# WeatherStation_V2.net
KiCad netlist of a schematic drawn in Altium Designer
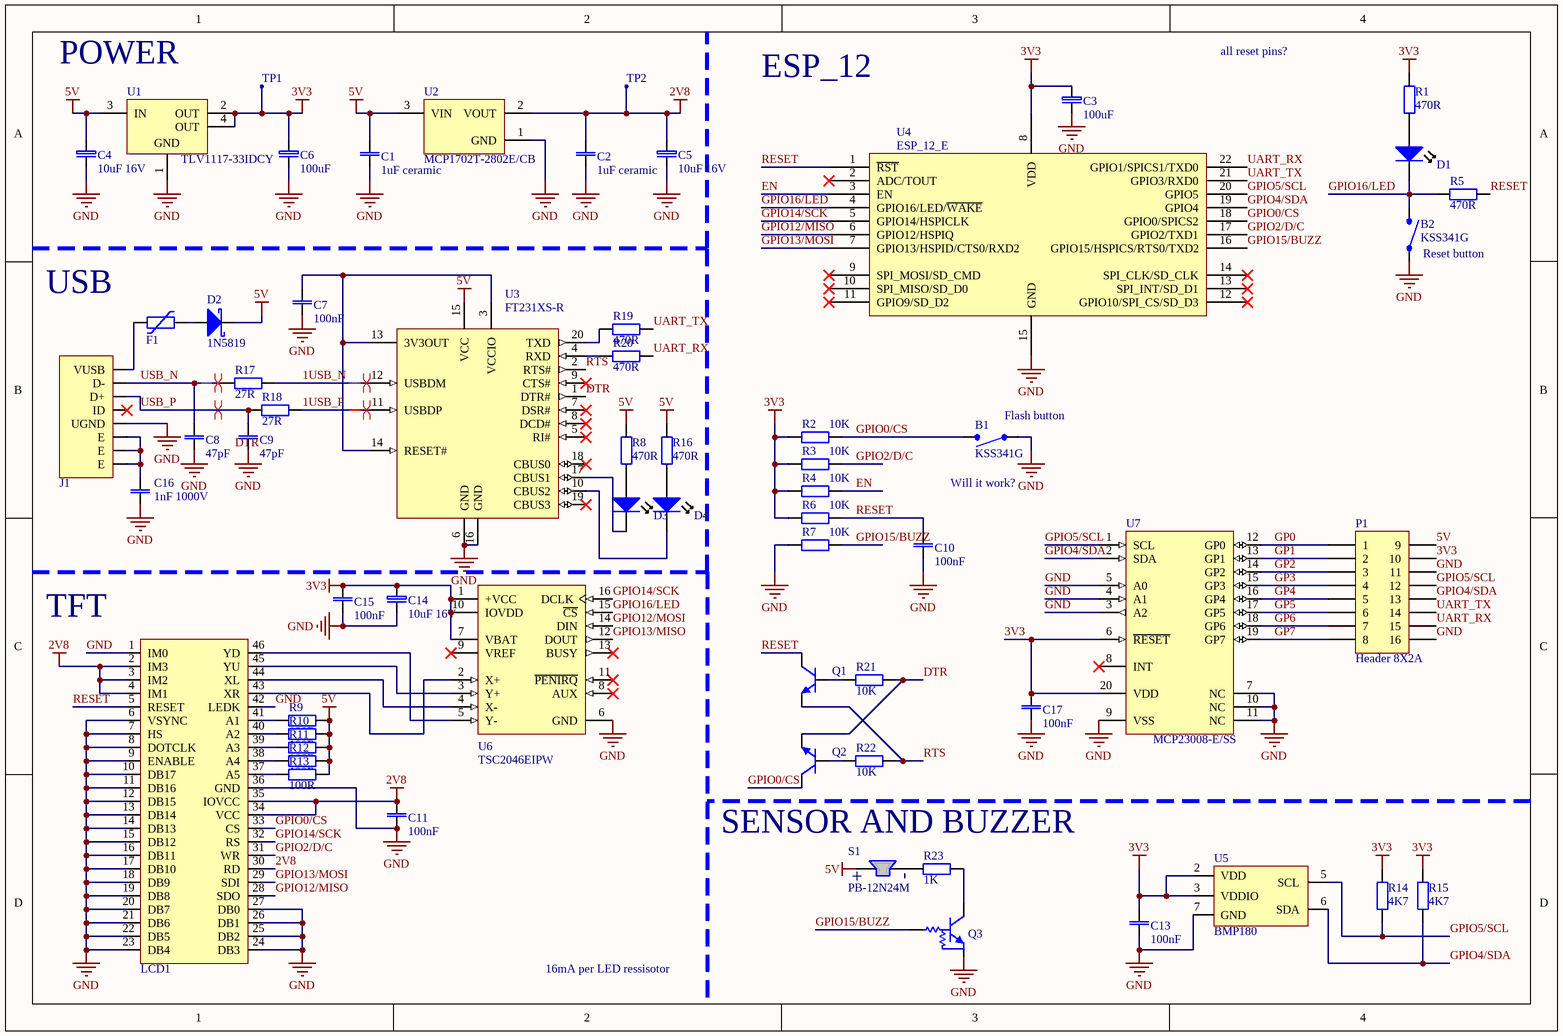
[diagram p0: WeatherStation_V2.SchDoc]

(export (version "E")
  (design (tool "Eeschema 10.0.6"))
  (components
    (comp (ref "B1")
      (value "KSS341G")
      (footprint "KSS341G")
      (description "side-mounted tactile button")
      (libsource (lib "DiscreteSchlib") (part "KSS341G"))
    )
    (comp (ref "B2")
      (value "KSS341G")
      (footprint "KSS341G")
      (description "side-mounted tactile button")
      (libsource (lib "DiscreteSchlib") (part "KSS341G"))
    )
    (comp (ref "C1")
      (value "1uF ceramic")
      (footprint "DiscretePcbLib:C0603")
      (description "SMD Capacitor")
      (libsource (lib "DiscreteSchlib") (part "C0603"))
    )
    (comp (ref "C2")
      (value "1uF ceramic")
      (footprint "DiscretePcbLib:C0603")
      (description "SMD Capacitor")
      (libsource (lib "DiscreteSchlib") (part "C0603"))
    )
    (comp (ref "C3")
      (value "100uF")
      (footprint "DiscretePcbLib:CASE B")
      (description "Tantalum capacitor")
      (libsource (lib "DiscreteSchlib") (part "Case B"))
    )
    (comp (ref "C4")
      (value "10uF 16V")
      (footprint "DiscretePcbLib:Case A")
      (description "Tantalum capacitor")
      (libsource (lib "DiscreteSchlib") (part "Case A"))
    )
    (comp (ref "C5")
      (value "10uF 16V")
      (footprint "DiscretePcbLib:Case A")
      (description "Tantalum capacitor")
      (libsource (lib "DiscreteSchlib") (part "Case A"))
    )
    (comp (ref "C6")
      (value "100uF")
      (footprint "DiscretePcbLib:CASE B")
      (description "Tantalum capacitor")
      (libsource (lib "DiscreteSchlib") (part "Case B"))
    )
    (comp (ref "C7")
      (value "100nF")
      (footprint "DiscretePcbLib:C0603")
      (description "SMD Capacitor")
      (libsource (lib "DiscreteSchlib") (part "C0603"))
    )
    (comp (ref "C8")
      (value "47pF")
      (footprint "DiscretePcbLib:C0603")
      (description "SMD Capacitor")
      (libsource (lib "DiscreteSchlib") (part "C0603"))
    )
    (comp (ref "C9")
      (value "47pF")
      (footprint "DiscretePcbLib:C0603")
      (description "SMD Capacitor")
      (libsource (lib "DiscreteSchlib") (part "C0603"))
    )
    (comp (ref "C10")
      (value "100nF")
      (footprint "DiscretePcbLib:C0603")
      (description "SMD Capacitor")
      (libsource (lib "DiscreteSchlib") (part "C0603"))
    )
    (comp (ref "C11")
      (value "100nF")
      (footprint "DiscretePcbLib:C0603")
      (description "SMD Capacitor")
      (libsource (lib "DiscreteSchlib") (part "C0603"))
    )
    (comp (ref "C13")
      (value "100nF")
      (footprint "DiscretePcbLib:C0603")
      (description "SMD Capacitor")
      (libsource (lib "DiscreteSchlib") (part "C0603"))
    )
    (comp (ref "C14")
      (value "10uF 16V")
      (footprint "DiscretePcbLib:Case A")
      (description "Tantalum capacitor")
      (libsource (lib "DiscreteSchlib") (part "Case A"))
    )
    (comp (ref "C15")
      (value "100nF")
      (footprint "DiscretePcbLib:C0603")
      (description "SMD Capacitor")
      (libsource (lib "DiscreteSchlib") (part "C0603"))
    )
    (comp (ref "C16")
      (value "1nF 1000V")
      (footprint "DiscretePcbLib:C1206")
      (description "SMD Capacitor")
      (libsource (lib "DiscreteSchlib") (part "C1206"))
    )
    (comp (ref "C17")
      (value "100nF")
      (footprint "DiscretePcbLib:C0603")
      (description "SMD Capacitor")
      (libsource (lib "DiscreteSchlib") (part "C0603"))
    )
    (comp (ref "D1")
      (value "BLUE LED")
      (footprint "DiscretePcbLib:LED0805B")
      (description "BLUE SMD LED 0805")
      (libsource (lib "DiscreteSchlib") (part "LED0805B"))
    )
    (comp (ref "D2")
      (value "1N5819")
      (footprint "1N5819-SMA")
      (description "40V 1A UFM0.5V/1A IFM30A IR0.4mA, Schottky")
      (libsource (lib "DiscreteSchlib") (part "1N5819(SS14)"))
    )
    (comp (ref "D3")
      (value "GREEN LED")
      (footprint "DiscretePcbLib:LED0805G")
      (description "GREEN SMD LED 0805")
      (libsource (lib "DiscreteSchlib") (part "LED0805G"))
    )
    (comp (ref "D4")
      (value "GREEN LED")
      (footprint "DiscretePcbLib:LED0805G")
      (description "GREEN SMD LED 0805")
      (libsource (lib "DiscreteSchlib") (part "LED0805G"))
    )
    (comp (ref "F1")
      (value "MF-MSMF075-2")
      (footprint "DiscretePcbLib:F1812")
      (description "Resettable Fuse 1812")
      (libsource (lib "DiscreteSchlib") (part "PFMF.XXX.X"))
    )
    (comp (ref "J1")
      (value "USB B MICRO R/A SMD 1")
      (footprint "DiscretePcbLib:USB B MICRO R/A SMD 1")
      (libsource (lib "DiscreteSchlib") (part "USB B MICRO R/A SMD 1"))
    )
    (comp (ref "LCD1")
      (value "KWH032ST05-F02")
      (footprint "KWH032ST05-F02")
      (libsource (lib "Schlib2") (part "KWH032ST05-F02"))
    )
    (comp (ref "P1")
      (value "Header 8X2A")
      (footprint "HDR2X8_CEN")
      (description "Header, 8-Pin, Dual row")
      (fields (field (name "PUBLISHER") "Altium Limited"))
      (libsource (lib "Miscellaneous Connectors") (part "Header 8X2A"))
    )
    (comp (ref "Q1")
      (value "BC817")
      (footprint "DiscretePcbLib:SOT23")
      (description "NPN SOT23")
      (libsource (lib "DiscreteSchlib") (part "BC817"))
    )
    (comp (ref "Q2")
      (value "BC817")
      (footprint "DiscretePcbLib:SOT23")
      (description "NPN SOT23")
      (libsource (lib "DiscreteSchlib") (part "BC817"))
    )
    (comp (ref "Q3")
      (value "PDTC123JT")
      (footprint "DiscretePcbLib:SOT23")
      (description "DIGI TRANS Rin 2.2k Rbe 47k NPN 50V 100mA")
      (libsource (lib "DiscreteSchlib") (part "PDTC123JT"))
    )
    (comp (ref "R1")
      (value "470R")
      (footprint "DiscretePcbLib:R0603")
      (description "SMD Resistor")
      (libsource (lib "") (part "R0603_2"))
    )
    (comp (ref "R2")
      (value "10K")
      (footprint "DiscretePcbLib:R0603")
      (description "SMD Resistor")
      (libsource (lib "DiscreteSchlib") (part "R0603"))
    )
    (comp (ref "R3")
      (value "10K")
      (footprint "DiscretePcbLib:R0603")
      (description "SMD Resistor")
      (libsource (lib "DiscreteSchlib") (part "R0603"))
    )
    (comp (ref "R4")
      (value "10K")
      (footprint "DiscretePcbLib:R0603")
      (description "SMD Resistor")
      (libsource (lib "DiscreteSchlib") (part "R0603"))
    )
    (comp (ref "R5")
      (value "470R")
      (footprint "DiscretePcbLib:R0603")
      (description "SMD Resistor")
      (libsource (lib "DiscreteSchlib") (part "R0603"))
    )
    (comp (ref "R6")
      (value "10K")
      (footprint "DiscretePcbLib:R0603")
      (description "SMD Resistor")
      (libsource (lib "DiscreteSchlib") (part "R0603"))
    )
    (comp (ref "R7")
      (value "10K")
      (footprint "DiscretePcbLib:R0603")
      (description "SMD Resistor")
      (libsource (lib "DiscreteSchlib") (part "R0603"))
    )
    (comp (ref "R8")
      (value "470R")
      (footprint "DiscretePcbLib:R0603")
      (description "SMD Resistor")
      (libsource (lib "") (part "R0603_1"))
    )
    (comp (ref "R9")
      (value "100R")
      (footprint "DiscretePcbLib:R0603")
      (description "SMD Resistor")
      (libsource (lib "DiscreteSchlib") (part "R0603"))
    )
    (comp (ref "R10")
      (value "100R")
      (footprint "DiscretePcbLib:R0603")
      (description "SMD Resistor")
      (libsource (lib "DiscreteSchlib") (part "R0603"))
    )
    (comp (ref "R11")
      (value "100R")
      (footprint "DiscretePcbLib:R0603")
      (description "SMD Resistor")
      (libsource (lib "DiscreteSchlib") (part "R0603"))
    )
    (comp (ref "R12")
      (value "100R")
      (footprint "DiscretePcbLib:R0603")
      (description "SMD Resistor")
      (libsource (lib "DiscreteSchlib") (part "R0603"))
    )
    (comp (ref "R13")
      (value "100R")
      (footprint "DiscretePcbLib:R0603")
      (description "SMD Resistor")
      (libsource (lib "DiscreteSchlib") (part "R0603"))
    )
    (comp (ref "R14")
      (value "4K7")
      (footprint "DiscretePcbLib:R0603")
      (description "SMD Resistor")
      (libsource (lib "") (part "R0603_1"))
    )
    (comp (ref "R15")
      (value "4K7")
      (footprint "DiscretePcbLib:R0603")
      (description "SMD Resistor")
      (libsource (lib "") (part "R0603_1"))
    )
    (comp (ref "R16")
      (value "470R")
      (footprint "DiscretePcbLib:R0603")
      (description "SMD Resistor")
      (libsource (lib "") (part "R0603_1"))
    )
    (comp (ref "R17")
      (value "27R")
      (footprint "DiscretePcbLib:R0603")
      (description "SMD Resistor")
      (libsource (lib "DiscreteSchlib") (part "R0603"))
    )
    (comp (ref "R18")
      (value "27R")
      (footprint "DiscretePcbLib:R0603")
      (description "SMD Resistor")
      (libsource (lib "DiscreteSchlib") (part "R0603"))
    )
    (comp (ref "R19")
      (value "470R")
      (footprint "DiscretePcbLib:R0603")
      (description "SMD Resistor")
      (libsource (lib "DiscreteSchlib") (part "R0603"))
    )
    (comp (ref "R20")
      (value "470R")
      (footprint "DiscretePcbLib:R0603")
      (description "SMD Resistor")
      (libsource (lib "DiscreteSchlib") (part "R0603"))
    )
    (comp (ref "R21")
      (value "10K")
      (footprint "DiscretePcbLib:R0603")
      (description "SMD Resistor")
      (libsource (lib "DiscreteSchlib") (part "R0603"))
    )
    (comp (ref "R22")
      (value "10K")
      (footprint "DiscretePcbLib:R0603")
      (description "SMD Resistor")
      (libsource (lib "DiscreteSchlib") (part "R0603"))
    )
    (comp (ref "R23")
      (value "1K")
      (footprint "DiscretePcbLib:R0603")
      (description "SMD Resistor")
      (libsource (lib "DiscreteSchlib") (part "R0603"))
    )
    (comp (ref "S1")
      (value "PB-12N24M")
      (footprint "PB-12N24M")
      (libsource (lib "DiscreteSchlib") (part "PB-12N24M"))
    )
    (comp (ref "TP1")
      (value "TestPoint_1.5mm")
      (footprint "DiscretePcbLib:TP_1.5mm")
      (description "TestPoint SMD pad 1.5mm")
      (libsource (lib "DiscreteSchlib") (part "TestPoint_1.5mm"))
    )
    (comp (ref "TP2")
      (value "TestPoint_1.5mm")
      (footprint "DiscretePcbLib:TP_1.5mm")
      (description "TestPoint SMD pad 1.5mm")
      (libsource (lib "DiscreteSchlib") (part "TestPoint_1.5mm"))
    )
    (comp (ref "U1")
      (value "TLV1117-33IDCY")
      (footprint "TI-DCY4_N")
      (fields (field (name "MANUFACTURER") "Texas Instruments") (field (name "PARTNUMBER") "TLV1117LV33DCYR"))
      (libsource (lib "TI Power Management Linear Regulator Single Channel LDO (400-7500mA)") (part "TLV1117LV33DCYR"))
    )
    (comp (ref "U2")
      (value "MCP1702T-2802E/CB")
      (footprint "SOT-23A-CB3_N")
      (description "250 mA Low Quiescent Current LDO Regulator, 3-Pin SOT-23A, Extended Temperature, Tape and Reel")
      (fields (field (name "MANUFACTURER") "Microchip"))
      (libsource (lib "Microchip Power Management Line Regulator") (part "MCP1702T-2802E/CB"))
    )
    (comp (ref "U3")
      (value "FT231XS-R")
      (footprint "SSOP-20_N")
      (fields (field (name "MANUFACTURER") "FTDI"))
      (libsource (lib "FTDI FT-X Series") (part "FT231XS-R"))
    )
    (comp (ref "U4")
      (value "ESP_12_E")
      (footprint "ESP-12Q/F")
      (description "ESP-12 Wi-Fi Module by AI-Thinker")
      (libsource (lib "DiscreteSchlib") (part "ESP_12_E"))
    )
    (comp (ref "U5")
      (value "BMP180")
      (footprint "BMP180")
      (description "temperature/pressure/altitude sensor")
      (libsource (lib "DiscreteSchlib") (part "BMP180"))
    )
    (comp (ref "U6")
      (value "TSC2046EIPW")
      (footprint "PW016")
      (description "4-Wire Touch Screen controller with Low-Voltage I/O Interface, 16-Pin TSSOP")
      (fields (field (name "PUBLISHER") "Altium Limited"))
      (libsource (lib "TI Interface Touch Screen Controller") (part "TSC2046EIPW"))
    )
    (comp (ref "U7")
      (value "MCP23008-E/SS")
      (footprint "SSOP-SS20_N")
      (description "8-Bit I/O Expander with Serial Interface, 20-Pin SSOP, Extended Temperature")
      (fields (field (name "MANUFACTURER") "Microchip"))
      (libsource (lib "Microchip Interface") (part "MCP23008-E/SS"))
    )
  )
  (nets
    (net (code "1") (name "/1USB_N") (class "Default")
      (node (ref "R17") (pin "2") (pinfunction "2_2") (pintype "passive"))
      (node (ref "U3") (pin "12") (pinfunction "USBDM_12") (pintype "input"))
    )
    (net (code "2") (name "/1USB_P") (class "Default")
      (node (ref "R18") (pin "2") (pinfunction "2_2") (pintype "passive"))
      (node (ref "U3") (pin "11") (pinfunction "USBDP_11") (pintype "input"))
    )
    (net (code "3") (name "/DTR") (class "Default")
      (node (ref "Q2") (pin "2") (pinfunction "2_2") (pintype "passive"))
      (node (ref "R21") (pin "2") (pinfunction "2_2") (pintype "passive"))
      (node (ref "U3") (pin "1") (pinfunction "DTR#_1") (pintype "output"))
    )
    (net (code "4") (name "/EN") (class "Default")
      (node (ref "R4") (pin "2") (pinfunction "2_2") (pintype "passive"))
      (node (ref "U4") (pin "3") (pinfunction "EN_3") (pintype "passive"))
    )
    (net (code "5") (name "/GP0") (class "Default")
      (node (ref "P1") (pin "1") (pinfunction "1_1") (pintype "passive"))
      (node (ref "U7") (pin "12") (pinfunction "GP0_12") (pintype "bidirectional"))
    )
    (net (code "6") (name "/GP1") (class "Default")
      (node (ref "P1") (pin "2") (pinfunction "2_2") (pintype "passive"))
      (node (ref "U7") (pin "13") (pinfunction "GP1_13") (pintype "bidirectional"))
    )
    (net (code "7") (name "/GP2") (class "Default")
      (node (ref "P1") (pin "3") (pinfunction "3_3") (pintype "passive"))
      (node (ref "U7") (pin "14") (pinfunction "GP2_14") (pintype "bidirectional"))
    )
    (net (code "8") (name "/GP3") (class "Default")
      (node (ref "P1") (pin "4") (pinfunction "4_4") (pintype "passive"))
      (node (ref "U7") (pin "15") (pinfunction "GP3_15") (pintype "bidirectional"))
    )
    (net (code "9") (name "/GP4") (class "Default")
      (node (ref "P1") (pin "5") (pinfunction "5_5") (pintype "passive"))
      (node (ref "U7") (pin "16") (pinfunction "GP4_16") (pintype "bidirectional"))
    )
    (net (code "10") (name "/GP5") (class "Default")
      (node (ref "P1") (pin "6") (pinfunction "6_6") (pintype "passive"))
      (node (ref "U7") (pin "17") (pinfunction "GP5_17") (pintype "bidirectional"))
    )
    (net (code "11") (name "/GP6") (class "Default")
      (node (ref "P1") (pin "7") (pinfunction "7_7") (pintype "passive"))
      (node (ref "U7") (pin "18") (pinfunction "GP6_18") (pintype "bidirectional"))
    )
    (net (code "12") (name "/GP7") (class "Default")
      (node (ref "P1") (pin "8") (pinfunction "8_8") (pintype "passive"))
      (node (ref "U7") (pin "19") (pinfunction "GP7_19") (pintype "bidirectional"))
    )
    (net (code "13") (name "/GPIO0{slash}CS") (class "Default")
      (node (ref "B1") (pin "2") (pinfunction "2_2") (pintype "passive"))
      (node (ref "LCD1") (pin "33") (pinfunction "CS_33") (pintype "passive"))
      (node (ref "Q2") (pin "3") (pinfunction "3_3") (pintype "passive"))
      (node (ref "R2") (pin "2") (pinfunction "2_2") (pintype "passive"))
      (node (ref "U4") (pin "18") (pinfunction "GPIO0/SPICS2_18") (pintype "passive"))
    )
    (net (code "14") (name "/GPIO2{slash}D{slash}C") (class "Default")
      (node (ref "LCD1") (pin "31") (pinfunction "WR_31") (pintype "passive"))
      (node (ref "R3") (pin "2") (pinfunction "2_2") (pintype "passive"))
      (node (ref "U4") (pin "17") (pinfunction "GPIO2/TXD1_17") (pintype "passive"))
    )
    (net (code "15") (name "/GPIO4{slash}SDA") (class "Default")
      (node (ref "P1") (pin "13") (pinfunction "13_13") (pintype "passive"))
      (node (ref "R15") (pin "1") (pinfunction "1_1") (pintype "passive"))
      (node (ref "U4") (pin "19") (pinfunction "GPIO4_19") (pintype "passive"))
      (node (ref "U5") (pin "6") (pinfunction "SDA_6") (pintype "passive"))
      (node (ref "U7") (pin "2") (pinfunction "SDA_2") (pintype "input"))
    )
    (net (code "16") (name "/GPIO5{slash}SCL") (class "Default")
      (node (ref "P1") (pin "12") (pinfunction "12_12") (pintype "passive"))
      (node (ref "R14") (pin "1") (pinfunction "1_1") (pintype "passive"))
      (node (ref "U4") (pin "20") (pinfunction "GPIO5_20") (pintype "passive"))
      (node (ref "U5") (pin "5") (pinfunction "SCL_5") (pintype "passive"))
      (node (ref "U7") (pin "1") (pinfunction "SCL_1") (pintype "input"))
    )
    (net (code "17") (name "/GPIO12{slash}MISO") (class "Default")
      (node (ref "LCD1") (pin "28") (pinfunction "SDO_28") (pintype "passive"))
      (node (ref "U4") (pin "6") (pinfunction "GPIO12/HSPIQ_6") (pintype "passive"))
    )
    (net (code "18") (name "/GPIO12{slash}MOSI") (class "Default")
      (node (ref "U6") (pin "14") (pinfunction "DIN_14") (pintype "input"))
    )
    (net (code "19") (name "/GPIO13{slash}MISO") (class "Default")
      (node (ref "U6") (pin "12") (pinfunction "DOUT_12") (pintype "output"))
    )
    (net (code "20") (name "/GPIO13{slash}MOSI") (class "Default")
      (node (ref "LCD1") (pin "29") (pinfunction "SDI_29") (pintype "passive"))
      (node (ref "U4") (pin "7") (pinfunction "GPIO13/HSPID/CTS0/RXD2_7") (pintype "passive"))
    )
    (net (code "21") (name "/GPIO14{slash}SCK") (class "Default")
      (node (ref "LCD1") (pin "32") (pinfunction "RS_32") (pintype "passive"))
      (node (ref "U4") (pin "5") (pinfunction "GPIO14/HSPICLK_5") (pintype "passive"))
      (node (ref "U6") (pin "16") (pinfunction "DCLK_16") (pintype "input"))
    )
    (net (code "22") (name "/GPIO15{slash}BUZZ") (class "Default")
      (node (ref "Q3") (pin "1") (pinfunction "1_1") (pintype "passive"))
      (node (ref "R7") (pin "2") (pinfunction "2_2") (pintype "passive"))
      (node (ref "U4") (pin "16") (pinfunction "GPIO15/HSPICS/RTS0/TXD2_16") (pintype "passive"))
    )
    (net (code "23") (name "/GPIO16{slash}LED") (class "Default")
      (node (ref "B2") (pin "2") (pinfunction "2_2") (pintype "passive"))
      (node (ref "D1") (pin "1") (pinfunction "1_1") (pintype "passive"))
      (node (ref "R5") (pin "1") (pinfunction "1_1") (pintype "passive"))
      (node (ref "U4") (pin "4") (pinfunction "GPIO16/LED/~{WAKE}_4") (pintype "passive"))
      (node (ref "U6") (pin "15") (pinfunction "~{CS}_15") (pintype "input"))
    )
    (net (code "24") (name "/RESET") (class "Default")
      (node (ref "C10") (pin "2") (pinfunction "2_2") (pintype "passive"))
      (node (ref "LCD1") (pin "5") (pinfunction "RESET_5") (pintype "passive"))
      (node (ref "Q1") (pin "3") (pinfunction "3_3") (pintype "passive"))
      (node (ref "R5") (pin "2") (pinfunction "2_2") (pintype "passive"))
      (node (ref "R6") (pin "2") (pinfunction "2_2") (pintype "passive"))
      (node (ref "U4") (pin "1") (pinfunction "~{RST}_1") (pintype "passive"))
    )
    (net (code "25") (name "/RTS") (class "Default")
      (node (ref "Q1") (pin "2") (pinfunction "2_2") (pintype "passive"))
      (node (ref "R22") (pin "2") (pinfunction "2_2") (pintype "passive"))
      (node (ref "U3") (pin "2") (pinfunction "RTS#_2") (pintype "output"))
    )
    (net (code "26") (name "/UART_RX") (class "Default")
      (node (ref "P1") (pin "15") (pinfunction "15_15") (pintype "passive"))
      (node (ref "R20") (pin "2") (pinfunction "2_2") (pintype "passive"))
      (node (ref "U4") (pin "22") (pinfunction "GPIO1/SPICS1/TXD0_22") (pintype "passive"))
    )
    (net (code "27") (name "/UART_TX") (class "Default")
      (node (ref "P1") (pin "14") (pinfunction "14_14") (pintype "passive"))
      (node (ref "R19") (pin "2") (pinfunction "2_2") (pintype "passive"))
      (node (ref "U4") (pin "21") (pinfunction "GPIO3/RXD0_21") (pintype "passive"))
    )
    (net (code "28") (name "/USB_N") (class "Default")
      (node (ref "C8") (pin "2") (pinfunction "2_2") (pintype "passive"))
      (node (ref "J1") (pin "2") (pinfunction "D-_2") (pintype "passive"))
      (node (ref "R17") (pin "1") (pinfunction "1_1") (pintype "passive"))
    )
    (net (code "29") (name "/USB_P") (class "Default")
      (node (ref "C9") (pin "2") (pinfunction "2_2") (pintype "passive"))
      (node (ref "J1") (pin "3") (pinfunction "D+_3") (pintype "passive"))
      (node (ref "R18") (pin "1") (pinfunction "1_1") (pintype "passive"))
    )
    (net (code "30") (name "2V8") (class "Default")
      (node (ref "C11") (pin "2") (pinfunction "2_2") (pintype "passive"))
      (node (ref "C2") (pin "2") (pinfunction "2_2") (pintype "passive"))
      (node (ref "C5") (pin "1") (pinfunction "1_1") (pintype "passive"))
      (node (ref "LCD1") (pin "2") (pinfunction "IM3_2") (pintype "passive"))
      (node (ref "LCD1") (pin "3") (pinfunction "IM2_3") (pintype "passive"))
      (node (ref "LCD1") (pin "30") (pinfunction "RD_30") (pintype "passive"))
      (node (ref "LCD1") (pin "34") (pinfunction "VCC_34") (pintype "passive"))
      (node (ref "LCD1") (pin "35") (pinfunction "IOVCC_35") (pintype "passive"))
      (node (ref "LCD1") (pin "4") (pinfunction "IM1_4") (pintype "passive"))
      (node (ref "TP2") (pin "1") (pinfunction "1_1") (pintype "passive"))
      (node (ref "U2") (pin "2") (pinfunction "VOUT_2") (pintype "power_in"))
    )
    (net (code "31") (name "3V3") (class "Default")
      (node (ref "C13") (pin "2") (pinfunction "2_2") (pintype "passive"))
      (node (ref "C14") (pin "1") (pinfunction "1_1") (pintype "passive"))
      (node (ref "C15") (pin "2") (pinfunction "2_2") (pintype "passive"))
      (node (ref "C17") (pin "2") (pinfunction "2_2") (pintype "passive"))
      (node (ref "C3") (pin "1") (pinfunction "1_1") (pintype "passive"))
      (node (ref "C6") (pin "1") (pinfunction "1_1") (pintype "passive"))
      (node (ref "P1") (pin "10") (pinfunction "10_10") (pintype "passive"))
      (node (ref "R1") (pin "1") (pinfunction "1_1") (pintype "passive"))
      (node (ref "R14") (pin "2") (pinfunction "2_2") (pintype "passive"))
      (node (ref "R15") (pin "2") (pinfunction "2_2") (pintype "passive"))
      (node (ref "R2") (pin "1") (pinfunction "1_1") (pintype "passive"))
      (node (ref "R3") (pin "1") (pinfunction "1_1") (pintype "passive"))
      (node (ref "R4") (pin "1") (pinfunction "1_1") (pintype "passive"))
      (node (ref "R6") (pin "1") (pinfunction "1_1") (pintype "passive"))
      (node (ref "TP1") (pin "1") (pinfunction "1_1") (pintype "passive"))
      (node (ref "U1") (pin "2") (pinfunction "OUT_2") (pintype "power_in"))
      (node (ref "U1") (pin "4") (pinfunction "OUT_4") (pintype "power_in"))
      (node (ref "U4") (pin "8") (pinfunction "VDD_8") (pintype "passive"))
      (node (ref "U5") (pin "2") (pinfunction "VDD_2") (pintype "passive"))
      (node (ref "U5") (pin "3") (pinfunction "VDDIO_3") (pintype "passive"))
      (node (ref "U6") (pin "1") (pinfunction "+VCC_1") (pintype "power_in"))
      (node (ref "U6") (pin "10") (pinfunction "IOVDD_10") (pintype "power_in"))
      (node (ref "U6") (pin "7") (pinfunction "VBAT_7") (pintype "power_in"))
      (node (ref "U7") (pin "20") (pinfunction "VDD_20") (pintype "power_in"))
      (node (ref "U7") (pin "6") (pinfunction "~{RESET}_6") (pintype "input"))
    )
    (net (code "32") (name "5V") (class "Default")
      (node (ref "C1") (pin "2") (pinfunction "2_2") (pintype "passive"))
      (node (ref "C4") (pin "1") (pinfunction "1_1") (pintype "passive"))
      (node (ref "D2") (pin "1") (pinfunction "1_1") (pintype "passive"))
      (node (ref "P1") (pin "9") (pinfunction "9_9") (pintype "passive"))
      (node (ref "R10") (pin "2") (pinfunction "2_2") (pintype "passive"))
      (node (ref "R11") (pin "2") (pinfunction "2_2") (pintype "passive"))
      (node (ref "R12") (pin "2") (pinfunction "2_2") (pintype "passive"))
      (node (ref "R13") (pin "2") (pinfunction "2_2") (pintype "passive"))
      (node (ref "R16") (pin "2") (pinfunction "2_2") (pintype "passive"))
      (node (ref "R8") (pin "2") (pinfunction "2_2") (pintype "passive"))
      (node (ref "R9") (pin "2") (pinfunction "2_2") (pintype "passive"))
      (node (ref "S1") (pin "1") (pinfunction "+_1") (pintype "passive"))
      (node (ref "U1") (pin "3") (pinfunction "IN_3") (pintype "power_in"))
      (node (ref "U2") (pin "3") (pinfunction "VIN_3") (pintype "power_in"))
      (node (ref "U3") (pin "15") (pinfunction "VCC_15") (pintype "power_in"))
    )
    (net (code "33") (name "GND") (class "Default")
      (node (ref "B1") (pin "1") (pinfunction "1_1") (pintype "passive"))
      (node (ref "B2") (pin "1") (pinfunction "1_1") (pintype "passive"))
      (node (ref "C1") (pin "1") (pinfunction "1_1") (pintype "passive"))
      (node (ref "C10") (pin "1") (pinfunction "1_1") (pintype "passive"))
      (node (ref "C11") (pin "1") (pinfunction "1_1") (pintype "passive"))
      (node (ref "C13") (pin "1") (pinfunction "1_1") (pintype "passive"))
      (node (ref "C14") (pin "2") (pinfunction "2_2") (pintype "passive"))
      (node (ref "C15") (pin "1") (pinfunction "1_1") (pintype "passive"))
      (node (ref "C16") (pin "1") (pinfunction "1_1") (pintype "passive"))
      (node (ref "C17") (pin "1") (pinfunction "1_1") (pintype "passive"))
      (node (ref "C2") (pin "1") (pinfunction "1_1") (pintype "passive"))
      (node (ref "C3") (pin "2") (pinfunction "2_2") (pintype "passive"))
      (node (ref "C4") (pin "2") (pinfunction "2_2") (pintype "passive"))
      (node (ref "C5") (pin "2") (pinfunction "2_2") (pintype "passive"))
      (node (ref "C6") (pin "2") (pinfunction "2_2") (pintype "passive"))
      (node (ref "C7") (pin "1") (pinfunction "1_1") (pintype "passive"))
      (node (ref "C8") (pin "1") (pinfunction "1_1") (pintype "passive"))
      (node (ref "C9") (pin "1") (pinfunction "1_1") (pintype "passive"))
      (node (ref "J1") (pin "5") (pinfunction "UGND_5") (pintype "passive"))
      (node (ref "LCD1") (pin "1") (pinfunction "IM0_1") (pintype "passive"))
      (node (ref "LCD1") (pin "10") (pinfunction "DB17_10") (pintype "passive"))
      (node (ref "LCD1") (pin "11") (pinfunction "DB16_11") (pintype "passive"))
      (node (ref "LCD1") (pin "12") (pinfunction "DB15_12") (pintype "passive"))
      (node (ref "LCD1") (pin "13") (pinfunction "DB14_13") (pintype "passive"))
      (node (ref "LCD1") (pin "14") (pinfunction "DB13_14") (pintype "passive"))
      (node (ref "LCD1") (pin "15") (pinfunction "DB12_15") (pintype "passive"))
      (node (ref "LCD1") (pin "16") (pinfunction "DB11_16") (pintype "passive"))
      (node (ref "LCD1") (pin "17") (pinfunction "DB10_17") (pintype "passive"))
      (node (ref "LCD1") (pin "18") (pinfunction "DB9_18") (pintype "passive"))
      (node (ref "LCD1") (pin "19") (pinfunction "DB8_19") (pintype "passive"))
      (node (ref "LCD1") (pin "20") (pinfunction "DB7_20") (pintype "passive"))
      (node (ref "LCD1") (pin "21") (pinfunction "DB6_21") (pintype "passive"))
      (node (ref "LCD1") (pin "22") (pinfunction "DB5_22") (pintype "passive"))
      (node (ref "LCD1") (pin "23") (pinfunction "DB4_23") (pintype "passive"))
      (node (ref "LCD1") (pin "24") (pinfunction "DB3_24") (pintype "passive"))
      (node (ref "LCD1") (pin "25") (pinfunction "DB2_25") (pintype "passive"))
      (node (ref "LCD1") (pin "26") (pinfunction "DB1_26") (pintype "passive"))
      (node (ref "LCD1") (pin "27") (pinfunction "DB0_27") (pintype "passive"))
      (node (ref "LCD1") (pin "36") (pinfunction "GND_36") (pintype "passive"))
      (node (ref "LCD1") (pin "42") (pinfunction "LEDK_42") (pintype "passive"))
      (node (ref "LCD1") (pin "6") (pinfunction "VSYNC_6") (pintype "passive"))
      (node (ref "LCD1") (pin "7") (pinfunction "HS_7") (pintype "passive"))
      (node (ref "LCD1") (pin "8") (pinfunction "DOTCLK_8") (pintype "passive"))
      (node (ref "LCD1") (pin "9") (pinfunction "ENABLE_9") (pintype "passive"))
      (node (ref "P1") (pin "11") (pinfunction "11_11") (pintype "passive"))
      (node (ref "P1") (pin "16") (pinfunction "16_16") (pintype "passive"))
      (node (ref "Q3") (pin "2") (pinfunction "2_2") (pintype "passive"))
      (node (ref "R7") (pin "1") (pinfunction "1_1") (pintype "passive"))
      (node (ref "U1") (pin "1") (pinfunction "GND_1") (pintype "power_in"))
      (node (ref "U2") (pin "1") (pinfunction "GND_1") (pintype "power_in"))
      (node (ref "U3") (pin "16") (pinfunction "GND_16") (pintype "power_in"))
      (node (ref "U3") (pin "6") (pinfunction "GND_6") (pintype "power_in"))
      (node (ref "U4") (pin "15") (pinfunction "GND_15") (pintype "passive"))
      (node (ref "U5") (pin "7") (pinfunction "GND_7") (pintype "passive"))
      (node (ref "U6") (pin "6") (pinfunction "GND_6") (pintype "power_in"))
      (node (ref "U7") (pin "10") (pinfunction "NC_10") (pintype "passive"))
      (node (ref "U7") (pin "11") (pinfunction "NC_11") (pintype "passive"))
      (node (ref "U7") (pin "3") (pinfunction "A2_3") (pintype "output"))
      (node (ref "U7") (pin "4") (pinfunction "A1_4") (pintype "input"))
      (node (ref "U7") (pin "5") (pinfunction "A0_5") (pintype "input"))
      (node (ref "U7") (pin "7") (pinfunction "NC_7") (pintype "passive"))
      (node (ref "U7") (pin "9") (pinfunction "VSS_9") (pintype "power_in"))
    )
    (net (code "34") (name "Net-(C16-Pad2)") (class "Default")
      (node (ref "C16") (pin "2") (pinfunction "2_2") (pintype "passive"))
      (node (ref "J1") (pin "6") (pinfunction "E_6") (pintype "passive"))
      (node (ref "J1") (pin "7") (pinfunction "E_7") (pintype "passive"))
      (node (ref "J1") (pin "8") (pinfunction "E_8") (pintype "passive"))
    )
    (net (code "35") (name "Net-(D1-Pad2)") (class "Default")
      (node (ref "D1") (pin "2") (pinfunction "2_2") (pintype "passive"))
      (node (ref "R1") (pin "2") (pinfunction "2_2") (pintype "passive"))
    )
    (net (code "36") (name "Net-(D2-Pad2)") (class "Default")
      (node (ref "D2") (pin "2") (pinfunction "2_2") (pintype "passive"))
      (node (ref "F1") (pin "2") (pinfunction "2_2") (pintype "passive"))
    )
    (net (code "37") (name "Net-(D3-Pad2)") (class "Default")
      (node (ref "D3") (pin "2") (pinfunction "2_2") (pintype "passive"))
      (node (ref "R8") (pin "1") (pinfunction "1_1") (pintype "passive"))
    )
    (net (code "38") (name "Net-(D4-Pad2)") (class "Default")
      (node (ref "D4") (pin "2") (pinfunction "2_2") (pintype "passive"))
      (node (ref "R16") (pin "1") (pinfunction "1_1") (pintype "passive"))
    )
    (net (code "39") (name "Net-(J1-VUSB)") (class "Default")
      (node (ref "F1") (pin "1") (pinfunction "1_1") (pintype "passive"))
      (node (ref "J1") (pin "1") (pinfunction "VUSB_1") (pintype "passive"))
    )
    (net (code "40") (name "Net-(LCD1-A1)") (class "Default")
      (node (ref "LCD1") (pin "41") (pinfunction "A1_41") (pintype "passive"))
      (node (ref "R9") (pin "1") (pinfunction "1_1") (pintype "passive"))
    )
    (net (code "41") (name "Net-(LCD1-A2)") (class "Default")
      (node (ref "LCD1") (pin "40") (pinfunction "A2_40") (pintype "passive"))
      (node (ref "R10") (pin "1") (pinfunction "1_1") (pintype "passive"))
    )
    (net (code "42") (name "Net-(LCD1-A3)") (class "Default")
      (node (ref "LCD1") (pin "39") (pinfunction "A3_39") (pintype "passive"))
      (node (ref "R11") (pin "1") (pinfunction "1_1") (pintype "passive"))
    )
    (net (code "43") (name "Net-(LCD1-A4)") (class "Default")
      (node (ref "LCD1") (pin "38") (pinfunction "A4_38") (pintype "passive"))
      (node (ref "R12") (pin "1") (pinfunction "1_1") (pintype "passive"))
    )
    (net (code "44") (name "Net-(LCD1-A5)") (class "Default")
      (node (ref "LCD1") (pin "37") (pinfunction "A5_37") (pintype "passive"))
      (node (ref "R13") (pin "1") (pinfunction "1_1") (pintype "passive"))
    )
    (net (code "45") (name "Net-(LCD1-XL)") (class "Default")
      (node (ref "LCD1") (pin "44") (pinfunction "XL_44") (pintype "passive"))
      (node (ref "U6") (pin "4") (pinfunction "X-_4") (pintype "input"))
    )
    (net (code "46") (name "Net-(LCD1-XR)") (class "Default")
      (node (ref "LCD1") (pin "43") (pinfunction "XR_43") (pintype "passive"))
      (node (ref "U6") (pin "2") (pinfunction "X+_2") (pintype "input"))
    )
    (net (code "47") (name "Net-(LCD1-YD)") (class "Default")
      (node (ref "LCD1") (pin "46") (pinfunction "YD_46") (pintype "passive"))
      (node (ref "U6") (pin "5") (pinfunction "Y-_5") (pintype "input"))
    )
    (net (code "48") (name "Net-(LCD1-YU)") (class "Default")
      (node (ref "LCD1") (pin "45") (pinfunction "YU_45") (pintype "passive"))
      (node (ref "U6") (pin "3") (pinfunction "Y+_3") (pintype "input"))
    )
    (net (code "49") (name "Net-(Q1-Pad1)") (class "Default")
      (node (ref "Q1") (pin "1") (pinfunction "1_1") (pintype "passive"))
      (node (ref "R21") (pin "1") (pinfunction "1_1") (pintype "passive"))
    )
    (net (code "50") (name "Net-(Q2-Pad1)") (class "Default")
      (node (ref "Q2") (pin "1") (pinfunction "1_1") (pintype "passive"))
      (node (ref "R22") (pin "1") (pinfunction "1_1") (pintype "passive"))
    )
    (net (code "51") (name "Net-(Q3-Pad3)") (class "Default")
      (node (ref "Q3") (pin "3") (pinfunction "3_3") (pintype "passive"))
      (node (ref "R23") (pin "2") (pinfunction "2_2") (pintype "passive"))
    )
    (net (code "52") (name "Net-(S1--)") (class "Default")
      (node (ref "R23") (pin "1") (pinfunction "1_1") (pintype "passive"))
      (node (ref "S1") (pin "2") (pinfunction "-_2") (pintype "passive"))
    )
    (net (code "53") (name "Net-(U3-3V3OUT)") (class "Default")
      (node (ref "C7") (pin "2") (pinfunction "2_2") (pintype "passive"))
      (node (ref "U3") (pin "13") (pinfunction "3V3OUT_13") (pintype "power_in"))
      (node (ref "U3") (pin "14") (pinfunction "RESET#_14") (pintype "input"))
      (node (ref "U3") (pin "3") (pinfunction "VCCIO_3") (pintype "power_in"))
    )
    (net (code "54") (name "Net-(U3-CBUS1)") (class "Default")
      (node (ref "D3") (pin "1") (pinfunction "1_1") (pintype "passive"))
      (node (ref "U3") (pin "17") (pinfunction "CBUS1_17") (pintype "bidirectional"))
    )
    (net (code "55") (name "Net-(U3-CBUS2)") (class "Default")
      (node (ref "D4") (pin "1") (pinfunction "1_1") (pintype "passive"))
      (node (ref "U3") (pin "10") (pinfunction "CBUS2_10") (pintype "bidirectional"))
    )
    (net (code "56") (name "Net-(U3-RXD)") (class "Default")
      (node (ref "R20") (pin "1") (pinfunction "1_1") (pintype "passive"))
      (node (ref "U3") (pin "4") (pinfunction "RXD_4") (pintype "input"))
    )
    (net (code "57") (name "Net-(U3-TXD)") (class "Default")
      (node (ref "R19") (pin "1") (pinfunction "1_1") (pintype "passive"))
      (node (ref "U3") (pin "20") (pinfunction "TXD_20") (pintype "output"))
    )
    (net (code "58") (name "unconnected-(J1-ID-Pad4)") (class "Default")
      (node (ref "J1") (pin "4") (pinfunction "ID_4") (pintype "passive+no_connect"))
    )
    (net (code "59") (name "unconnected-(U3-CBUS0-Pad18)") (class "Default")
      (node (ref "U3") (pin "18") (pinfunction "CBUS0_18") (pintype "bidirectional+no_connect"))
    )
    (net (code "60") (name "unconnected-(U3-CBUS3-Pad19)") (class "Default")
      (node (ref "U3") (pin "19") (pinfunction "CBUS3_19") (pintype "bidirectional+no_connect"))
    )
    (net (code "61") (name "unconnected-(U3-CTS#-Pad9)") (class "Default")
      (node (ref "U3") (pin "9") (pinfunction "CTS#_9") (pintype "input+no_connect"))
    )
    (net (code "62") (name "unconnected-(U3-DCD#-Pad8)") (class "Default")
      (node (ref "U3") (pin "8") (pinfunction "DCD#_8") (pintype "input+no_connect"))
    )
    (net (code "63") (name "unconnected-(U3-DSR#-Pad7)") (class "Default")
      (node (ref "U3") (pin "7") (pinfunction "DSR#_7") (pintype "input+no_connect"))
    )
    (net (code "64") (name "unconnected-(U3-RI#-Pad5)") (class "Default")
      (node (ref "U3") (pin "5") (pinfunction "RI#_5") (pintype "input+no_connect"))
    )
    (net (code "65") (name "unconnected-(U4-ADC{slash}TOUT-Pad2)") (class "Default")
      (node (ref "U4") (pin "2") (pinfunction "ADC/TOUT_2") (pintype "passive+no_connect"))
    )
    (net (code "66") (name "unconnected-(U4-GPIO9{slash}SD_D2-Pad11)") (class "Default")
      (node (ref "U4") (pin "11") (pinfunction "GPIO9/SD_D2_11") (pintype "passive+no_connect"))
    )
    (net (code "67") (name "unconnected-(U4-GPIO10{slash}SPI_CS{slash}SD_D3-Pad12)") (class "Default")
      (node (ref "U4") (pin "12") (pinfunction "GPIO10/SPI_CS/SD_D3_12") (pintype "passive+no_connect"))
    )
    (net (code "68") (name "unconnected-(U4-SPI_CLK{slash}SD_CLK-Pad14)") (class "Default")
      (node (ref "U4") (pin "14") (pinfunction "SPI_CLK/SD_CLK_14") (pintype "passive+no_connect"))
    )
    (net (code "69") (name "unconnected-(U4-SPI_INT{slash}SD_D1-Pad13)") (class "Default")
      (node (ref "U4") (pin "13") (pinfunction "SPI_INT/SD_D1_13") (pintype "passive+no_connect"))
    )
    (net (code "70") (name "unconnected-(U4-SPI_MISO{slash}SD_D0-Pad10)") (class "Default")
      (node (ref "U4") (pin "10") (pinfunction "SPI_MISO/SD_D0_10") (pintype "passive+no_connect"))
    )
    (net (code "71") (name "unconnected-(U4-SPI_MOSI{slash}SD_CMD-Pad9)") (class "Default")
      (node (ref "U4") (pin "9") (pinfunction "SPI_MOSI/SD_CMD_9") (pintype "passive+no_connect"))
    )
    (net (code "72") (name "unconnected-(U6-AUX-Pad8)") (class "Default")
      (node (ref "U6") (pin "8") (pinfunction "AUX_8") (pintype "input+no_connect"))
    )
    (net (code "73") (name "unconnected-(U6-BUSY-Pad13)") (class "Default")
      (node (ref "U6") (pin "13") (pinfunction "BUSY_13") (pintype "output+no_connect"))
    )
    (net (code "74") (name "unconnected-(U6-VREF-Pad9)") (class "Default")
      (node (ref "U6") (pin "9") (pinfunction "VREF_9") (pintype "power_in+no_connect"))
    )
    (net (code "75") (name "unconnected-(U6-~{PENIRQ}-Pad11)") (class "Default")
      (node (ref "U6") (pin "11") (pinfunction "~{PENIRQ}_11") (pintype "input+no_connect"))
    )
    (net (code "76") (name "unconnected-(U7-INT-Pad8)") (class "Default")
      (node (ref "U7") (pin "8") (pinfunction "INT_8") (pintype "open_collector+no_connect"))
    )
  )
)
